# GSM-Board.net
KiCad netlist of a schematic drawn in Altium Designer
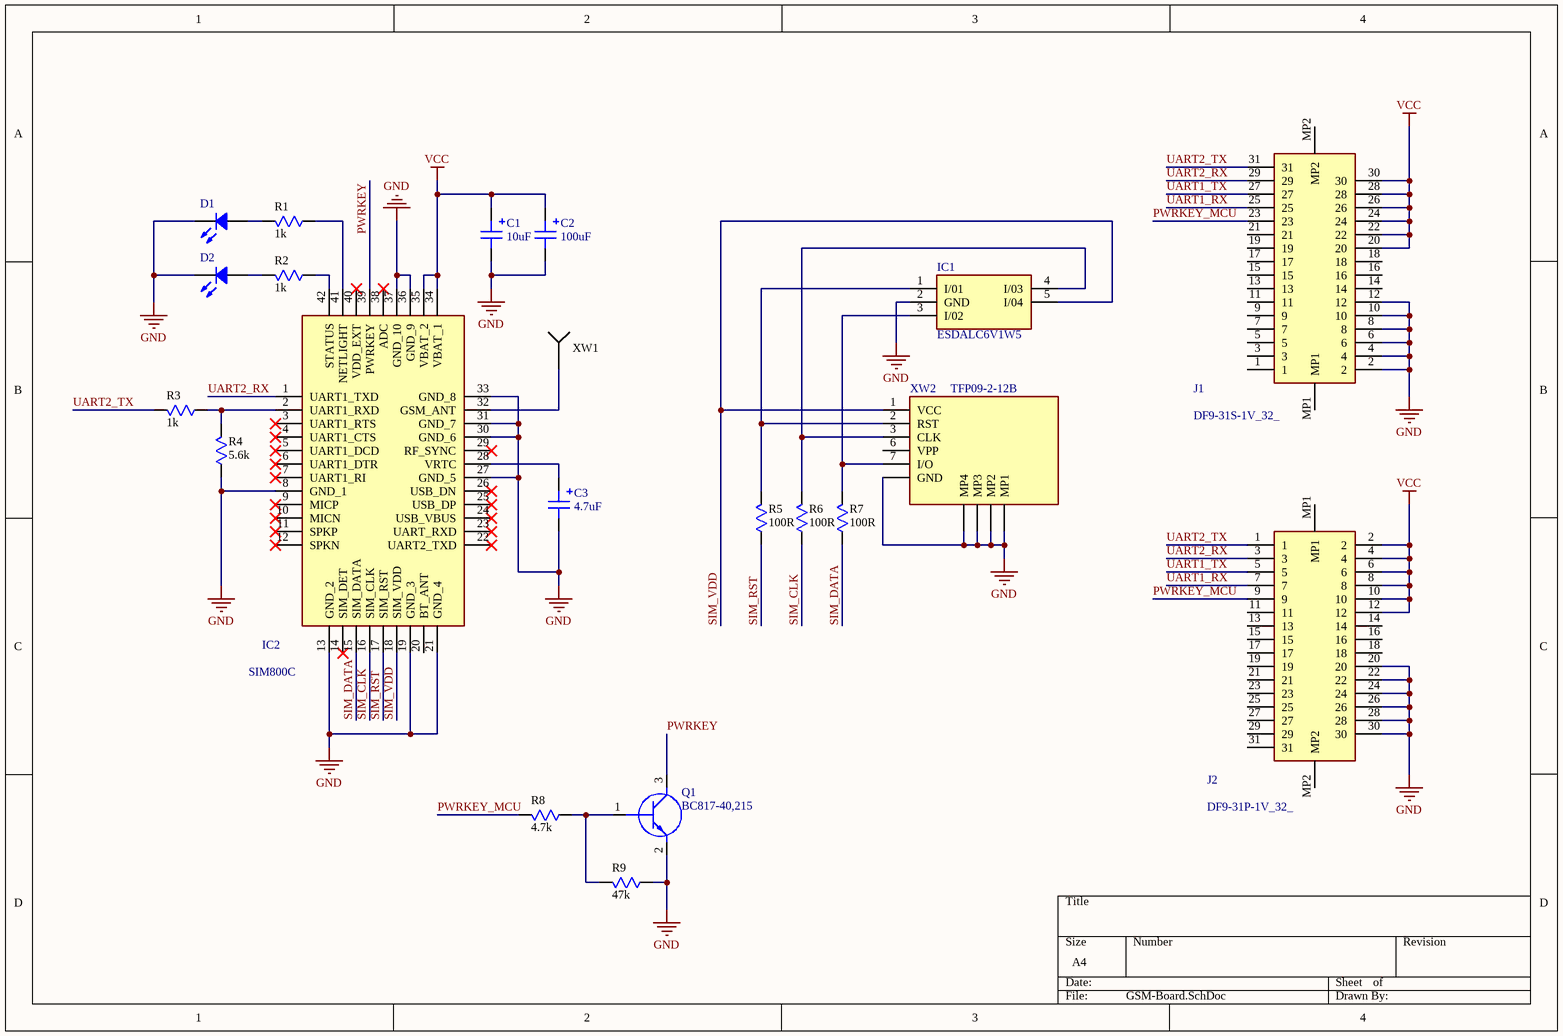
[diagram p0: GSM-Board.SchDoc]

(export (version "E")
  (design (tool "Eeschema 10.0.6"))
  (components
    (comp (ref "C1")
      (value "10uF")
      (footprint "PcbLib:CAP: TANTAL-B")
      (description "SMD Capacitor Polar")
      (libsource (lib "Schlib") (part "Capacitor_polar"))
    )
    (comp (ref "C2")
      (value "100uF")
      (footprint "PcbLib:CAP: TANTAL-D")
      (description "SMD Capacitor Polar")
      (libsource (lib "Schlib") (part "Capacitor_polar"))
    )
    (comp (ref "C3")
      (value "4.7uF")
      (footprint "PcbLib:CAP: TANTAL-A")
      (description "SMD Capacitor Polar")
      (libsource (lib "Schlib") (part "Capacitor_polar"))
    )
    (comp (ref "D1")
      (value "~")
      (footprint "PcbLib:LED0805")
      (description "Chip LED")
      (libsource (lib "Schlib") (part "LED"))
    )
    (comp (ref "D2")
      (value "~")
      (footprint "PcbLib:LED0805")
      (description "Chip LED")
      (libsource (lib "Schlib") (part "LED"))
    )
    (comp (ref "IC1")
      (value "ESDALC6V1W5")
      (footprint "PcbLib:SOT65P210X110-5N")
      (description "Integrated Circuit")
      (fields (field (name "MOUSER PART NUMBER") "511-ESDALC6V1W5"))
      (libsource (lib "*") (part "ESDALC6V1W5"))
    )
    (comp (ref "IC2")
      (value "SIM800C")
      (footprint "PcbLib:SIM800C")
      (description "Integrated Circuit")
      (fields (field (name "MANUFACTURER_PART_NUMBER") "-SIM800C"))
      (libsource (lib "Schlib") (part "-SIM800C"))
    )
    (comp (ref "J1")
      (value "DF9-31S-1V_32_")
      (footprint "PcbLib:DF931S1V32")
      (description "Connector")
      (fields
        (field (name "MANUFACTURER_PART_NUMBER") "DF9-31S-1V(32)")
        (field (name "MOUSER PART NUMBER") "798-DF9-31S-1V32")
      )
      (libsource (lib "Schlib") (part "DF9-31S-1V_32_"))
    )
    (comp (ref "J2")
      (value "DF9-31P-1V_32_")
      (footprint "PcbLib:DF931P1V32")
      (description "Connector")
      (fields
        (field (name "MANUFACTURER_PART_NUMBER") "DF9-31P-1V(32)")
        (field (name "MOUSER PART NUMBER") "798-DF9-31P-1V32")
      )
      (libsource (lib "Schlib") (part "DF9-31P-1V_32_"))
    )
    (comp (ref "Q1")
      (value "BC817-40,215")
      (footprint "PcbLib:BC81740215")
      (description "Transistor BJT NPN")
      (fields (field (name "MOUSER PART NUMBER") "771-BC817-40-T/R"))
      (libsource (lib "*") (part "BC817-40,215"))
    )
    (comp (ref "R1")
      (value "1k")
      (footprint "PcbLib:RES: 0805")
      (fields
        (field (name "MANUFACTURER") "Yageo")
        (field (name "PARTNUMBER") "RC0201JR-07100RL")
        (field (name "VALUEMANUFACTURERPARTNUMBER") "Resistor film, 1k, , 0201, 0.05W, -55...+125°C")
      )
      (libsource (lib "Schlib") (part "Resistor"))
    )
    (comp (ref "R2")
      (value "1k")
      (footprint "PcbLib:RES: 0805")
      (fields
        (field (name "MANUFACTURER") "Yageo")
        (field (name "PARTNUMBER") "RC0201JR-07100RL")
        (field (name "VALUEMANUFACTURERPARTNUMBER") "Resistor film, 1k, , 0201, 0.05W, -55...+125°C")
      )
      (libsource (lib "Schlib") (part "Resistor"))
    )
    (comp (ref "R3")
      (value "1k")
      (footprint "PcbLib:RES: 0805")
      (fields
        (field (name "MANUFACTURER") "Yageo")
        (field (name "PARTNUMBER") "RC0201JR-07100RL")
        (field (name "VALUEMANUFACTURERPARTNUMBER") "Resistor film, 1k, , 0201, 0.05W, -55...+125°C")
      )
      (libsource (lib "Schlib") (part "Resistor"))
    )
    (comp (ref "R4")
      (value "5.6k")
      (footprint "PcbLib:RES: 0805")
      (fields
        (field (name "MANUFACTURER") "Yageo")
        (field (name "PARTNUMBER") "RC0201JR-07100RL")
        (field (name "VALUEMANUFACTURERPARTNUMBER") "Resistor film, 5.6k, , 0201, 0.05W, -55...+125°C")
      )
      (libsource (lib "Schlib") (part "Resistor"))
    )
    (comp (ref "R5")
      (value "100R")
      (footprint "PcbLib:RES: 0805")
      (fields
        (field (name "MANUFACTURER") "Yageo")
        (field (name "PARTNUMBER") "RC0201JR-07100RL")
        (field (name "VALUEMANUFACTURERPARTNUMBER") "Resistor film, 100R, , 0201, 0.05W, -55...+125°C")
      )
      (libsource (lib "Schlib") (part "Resistor"))
    )
    (comp (ref "R6")
      (value "100R")
      (footprint "PcbLib:RES: 0805")
      (fields
        (field (name "MANUFACTURER") "Yageo")
        (field (name "PARTNUMBER") "RC0201JR-07100RL")
        (field (name "VALUEMANUFACTURERPARTNUMBER") "Resistor film, 100R, , 0201, 0.05W, -55...+125°C")
      )
      (libsource (lib "Schlib") (part "Resistor"))
    )
    (comp (ref "R7")
      (value "100R")
      (footprint "PcbLib:RES: 0805")
      (fields
        (field (name "MANUFACTURER") "Yageo")
        (field (name "PARTNUMBER") "RC0201JR-07100RL")
        (field (name "VALUEMANUFACTURERPARTNUMBER") "Resistor film, 100R, , 0201, 0.05W, -55...+125°C")
      )
      (libsource (lib "Schlib") (part "Resistor"))
    )
    (comp (ref "R8")
      (value "4.7k")
      (footprint "PcbLib:RES: 0805")
      (fields
        (field (name "MANUFACTURER") "Yageo")
        (field (name "PARTNUMBER") "RC0201JR-07100RL")
        (field (name "VALUEMANUFACTURERPARTNUMBER") "Resistor film, 4.7k, , 0201, 0.05W, -55...+125°C")
      )
      (libsource (lib "Schlib") (part "Resistor"))
    )
    (comp (ref "R9")
      (value "47k")
      (footprint "PcbLib:RES: 0805")
      (fields
        (field (name "MANUFACTURER") "Yageo")
        (field (name "PARTNUMBER") "RC0201JR-07100RL")
        (field (name "VALUEMANUFACTURERPARTNUMBER") "Resistor film, 47k, , 0201, 0.05W, -55...+125°C")
      )
      (libsource (lib "Schlib") (part "Resistor"))
    )
    (comp (ref "XW1")
      (value "~")
      (footprint "PcbLib:ANT_HOLE")
      (libsource (lib "Schlib") (part "Connector RF"))
    )
    (comp (ref "XW2")
      (value "TFP09-2-12B")
      (footprint "PcbLib:SIMHOLDER")
      (description "Connector")
      (libsource (lib "Schlib") (part "TFP09-2-12B"))
    )
  )
  (nets
    (net (code "1") (name "/PWRKEY") (class "Default")
      (node (ref "IC2") (pin "39") (pinfunction "PWRKEY_39") (pintype "passive"))
      (node (ref "Q1") (pin "3") (pinfunction "C_3") (pintype "passive"))
    )
    (net (code "2") (name "/PWRKEY_MCU") (class "Default")
      (node (ref "J1") (pin "23") (pinfunction "23_23") (pintype "passive"))
      (node (ref "J2") (pin "9") (pinfunction "9_9") (pintype "passive"))
      (node (ref "R8") (pin "2") (pinfunction "2_2") (pintype "passive"))
    )
    (net (code "3") (name "/SIM_CLK") (class "Default")
      (node (ref "IC2") (pin "16") (pinfunction "SIM_CLK_16") (pintype "passive"))
      (node (ref "R6") (pin "1") (pinfunction "1_1") (pintype "passive"))
    )
    (net (code "4") (name "/SIM_DATA") (class "Default")
      (node (ref "IC2") (pin "15") (pinfunction "SIM_DATA_15") (pintype "passive"))
      (node (ref "R7") (pin "1") (pinfunction "1_1") (pintype "passive"))
    )
    (net (code "5") (name "/SIM_RST") (class "Default")
      (node (ref "IC2") (pin "17") (pinfunction "SIM_RST_17") (pintype "passive"))
      (node (ref "R5") (pin "1") (pinfunction "1_1") (pintype "passive"))
    )
    (net (code "6") (name "/SIM_VDD") (class "Default")
      (node (ref "IC1") (pin "5") (pinfunction "I/04_5") (pintype "passive"))
      (node (ref "IC2") (pin "18") (pinfunction "SIM_VDD_18") (pintype "passive"))
      (node (ref "XW2") (pin "1") (pinfunction "VCC_1") (pintype "power_in"))
    )
    (net (code "7") (name "/UART1_RX") (class "Default")
      (node (ref "J1") (pin "25") (pinfunction "25_25") (pintype "passive"))
      (node (ref "J2") (pin "7") (pinfunction "7_7") (pintype "passive"))
    )
    (net (code "8") (name "/UART1_TX") (class "Default")
      (node (ref "J1") (pin "27") (pinfunction "27_27") (pintype "passive"))
      (node (ref "J2") (pin "5") (pinfunction "5_5") (pintype "passive"))
    )
    (net (code "9") (name "/UART2_RX") (class "Default")
      (node (ref "IC2") (pin "1") (pinfunction "UART1_TXD_1") (pintype "passive"))
      (node (ref "J1") (pin "29") (pinfunction "29_29") (pintype "passive"))
      (node (ref "J2") (pin "3") (pinfunction "3_3") (pintype "passive"))
    )
    (net (code "10") (name "/UART2_TX") (class "Default")
      (node (ref "J1") (pin "31") (pinfunction "31_31") (pintype "passive"))
      (node (ref "J2") (pin "1") (pinfunction "1_1") (pintype "passive"))
      (node (ref "R3") (pin "2") (pinfunction "2_2") (pintype "passive"))
    )
    (net (code "11") (name "GND") (class "Default")
      (node (ref "C1") (pin "2") (pinfunction "2_2") (pintype "passive"))
      (node (ref "C2") (pin "2") (pinfunction "2_2") (pintype "passive"))
      (node (ref "C3") (pin "2") (pinfunction "2_2") (pintype "passive"))
      (node (ref "D1") (pin "2") (pinfunction "2_2") (pintype "passive"))
      (node (ref "D2") (pin "2") (pinfunction "2_2") (pintype "passive"))
      (node (ref "IC1") (pin "2") (pinfunction "GND_2") (pintype "passive"))
      (node (ref "IC2") (pin "13") (pinfunction "GND_2_13") (pintype "passive"))
      (node (ref "IC2") (pin "19") (pinfunction "GND_3_19") (pintype "passive"))
      (node (ref "IC2") (pin "21") (pinfunction "GND_4_21") (pintype "passive"))
      (node (ref "IC2") (pin "27") (pinfunction "GND_5_27") (pintype "passive"))
      (node (ref "IC2") (pin "30") (pinfunction "GND_6_30") (pintype "passive"))
      (node (ref "IC2") (pin "31") (pinfunction "GND_7_31") (pintype "passive"))
      (node (ref "IC2") (pin "33") (pinfunction "GND_8_33") (pintype "passive"))
      (node (ref "IC2") (pin "36") (pinfunction "GND_9_36") (pintype "passive"))
      (node (ref "IC2") (pin "37") (pinfunction "GND_10_37") (pintype "passive"))
      (node (ref "IC2") (pin "8") (pinfunction "GND_1_8") (pintype "passive"))
      (node (ref "J1") (pin "10") (pinfunction "10_10") (pintype "passive"))
      (node (ref "J1") (pin "12") (pinfunction "12_12") (pintype "passive"))
      (node (ref "J1") (pin "2") (pinfunction "2_2") (pintype "passive"))
      (node (ref "J1") (pin "4") (pinfunction "4_4") (pintype "passive"))
      (node (ref "J1") (pin "6") (pinfunction "6_6") (pintype "passive"))
      (node (ref "J1") (pin "8") (pinfunction "8_8") (pintype "passive"))
      (node (ref "J2") (pin "20") (pinfunction "20_20") (pintype "passive"))
      (node (ref "J2") (pin "22") (pinfunction "22_22") (pintype "passive"))
      (node (ref "J2") (pin "24") (pinfunction "24_24") (pintype "passive"))
      (node (ref "J2") (pin "26") (pinfunction "26_26") (pintype "passive"))
      (node (ref "J2") (pin "28") (pinfunction "28_28") (pintype "passive"))
      (node (ref "J2") (pin "30") (pinfunction "30_30") (pintype "passive"))
      (node (ref "Q1") (pin "2") (pinfunction "E_2") (pintype "passive"))
      (node (ref "R4") (pin "1") (pinfunction "1_1") (pintype "passive"))
      (node (ref "R9") (pin "1") (pinfunction "1_1") (pintype "passive"))
      (node (ref "XW2") (pin "5") (pinfunction "GND_5") (pintype "power_in"))
      (node (ref "XW2") (pin "MP1") (pinfunction "MP1_MP1") (pintype "passive"))
      (node (ref "XW2") (pin "MP2") (pinfunction "MP2_MP2") (pintype "passive"))
      (node (ref "XW2") (pin "MP3") (pinfunction "MP3_MP3") (pintype "passive"))
      (node (ref "XW2") (pin "MP4") (pinfunction "MP4_MP4") (pintype "passive"))
    )
    (net (code "12") (name "Net-(D1-Pad1)") (class "Default")
      (node (ref "D1") (pin "1") (pinfunction "1_1") (pintype "passive"))
      (node (ref "R1") (pin "2") (pinfunction "2_2") (pintype "passive"))
    )
    (net (code "13") (name "Net-(D2-Pad1)") (class "Default")
      (node (ref "D2") (pin "1") (pinfunction "1_1") (pintype "passive"))
      (node (ref "R2") (pin "2") (pinfunction "2_2") (pintype "passive"))
    )
    (net (code "14") (name "Net-(IC1-I{slash}01)") (class "Default")
      (node (ref "IC1") (pin "1") (pinfunction "I/01_1") (pintype "passive"))
      (node (ref "R5") (pin "2") (pinfunction "2_2") (pintype "passive"))
      (node (ref "XW2") (pin "2") (pinfunction "RST_2") (pintype "passive"))
    )
    (net (code "15") (name "Net-(IC1-I{slash}02)") (class "Default")
      (node (ref "IC1") (pin "3") (pinfunction "I/02_3") (pintype "passive"))
      (node (ref "R7") (pin "2") (pinfunction "2_2") (pintype "passive"))
      (node (ref "XW2") (pin "7") (pinfunction "I/O_7") (pintype "passive"))
    )
    (net (code "16") (name "Net-(IC1-I{slash}03)") (class "Default")
      (node (ref "IC1") (pin "4") (pinfunction "I/03_4") (pintype "passive"))
      (node (ref "R6") (pin "2") (pinfunction "2_2") (pintype "passive"))
      (node (ref "XW2") (pin "3") (pinfunction "CLK_3") (pintype "passive"))
    )
    (net (code "17") (name "Net-(IC2-GSM_ANT)") (class "Default")
      (node (ref "IC2") (pin "32") (pinfunction "GSM_ANT_32") (pintype "passive"))
      (node (ref "XW1") (pin "1") (pinfunction "SIG_1") (pintype "passive"))
    )
    (net (code "18") (name "Net-(IC2-NETLIGHT)") (class "Default")
      (node (ref "IC2") (pin "41") (pinfunction "NETLIGHT_41") (pintype "passive"))
      (node (ref "R1") (pin "1") (pinfunction "1_1") (pintype "passive"))
    )
    (net (code "19") (name "Net-(IC2-STATUS)") (class "Default")
      (node (ref "IC2") (pin "42") (pinfunction "STATUS_42") (pintype "passive"))
      (node (ref "R2") (pin "1") (pinfunction "1_1") (pintype "passive"))
    )
    (net (code "20") (name "Net-(IC2-UART1_RXD)") (class "Default")
      (node (ref "IC2") (pin "2") (pinfunction "UART1_RXD_2") (pintype "passive"))
      (node (ref "R3") (pin "1") (pinfunction "1_1") (pintype "passive"))
      (node (ref "R4") (pin "2") (pinfunction "2_2") (pintype "passive"))
    )
    (net (code "21") (name "Net-(IC2-VRTC)") (class "Default")
      (node (ref "C3") (pin "1") (pinfunction "1_1") (pintype "passive"))
      (node (ref "IC2") (pin "28") (pinfunction "VRTC_28") (pintype "passive"))
    )
    (net (code "22") (name "Net-(Q1-B)") (class "Default")
      (node (ref "Q1") (pin "1") (pinfunction "B_1") (pintype "passive"))
      (node (ref "R8") (pin "1") (pinfunction "1_1") (pintype "passive"))
      (node (ref "R9") (pin "2") (pinfunction "2_2") (pintype "passive"))
    )
    (net (code "23") (name "VCC") (class "Default")
      (node (ref "C1") (pin "1") (pinfunction "1_1") (pintype "passive"))
      (node (ref "C2") (pin "1") (pinfunction "1_1") (pintype "passive"))
      (node (ref "IC2") (pin "34") (pinfunction "VBAT_1_34") (pintype "passive"))
      (node (ref "IC2") (pin "35") (pinfunction "VBAT_2_35") (pintype "passive"))
      (node (ref "J1") (pin "20") (pinfunction "20_20") (pintype "passive"))
      (node (ref "J1") (pin "22") (pinfunction "22_22") (pintype "passive"))
      (node (ref "J1") (pin "24") (pinfunction "24_24") (pintype "passive"))
      (node (ref "J1") (pin "26") (pinfunction "26_26") (pintype "passive"))
      (node (ref "J1") (pin "28") (pinfunction "28_28") (pintype "passive"))
      (node (ref "J1") (pin "30") (pinfunction "30_30") (pintype "passive"))
      (node (ref "J2") (pin "10") (pinfunction "10_10") (pintype "passive"))
      (node (ref "J2") (pin "12") (pinfunction "12_12") (pintype "passive"))
      (node (ref "J2") (pin "2") (pinfunction "2_2") (pintype "passive"))
      (node (ref "J2") (pin "4") (pinfunction "4_4") (pintype "passive"))
      (node (ref "J2") (pin "6") (pinfunction "6_6") (pintype "passive"))
      (node (ref "J2") (pin "8") (pinfunction "8_8") (pintype "passive"))
    )
    (net (code "24") (name "unconnected-(IC2-ADC-Pad38)") (class "Default")
      (node (ref "IC2") (pin "38") (pinfunction "ADC_38") (pintype "passive+no_connect"))
    )
    (net (code "25") (name "unconnected-(IC2-BT_ANT-Pad20)") (class "Default")
      (node (ref "IC2") (pin "20") (pinfunction "BT_ANT_20") (pintype "passive"))
    )
    (net (code "26") (name "unconnected-(IC2-MICN-Pad10)") (class "Default")
      (node (ref "IC2") (pin "10") (pinfunction "MICN_10") (pintype "passive+no_connect"))
    )
    (net (code "27") (name "unconnected-(IC2-MICP-Pad9)") (class "Default")
      (node (ref "IC2") (pin "9") (pinfunction "MICP_9") (pintype "passive+no_connect"))
    )
    (net (code "28") (name "unconnected-(IC2-RF_SYNC-Pad29)") (class "Default")
      (node (ref "IC2") (pin "29") (pinfunction "RF_SYNC_29") (pintype "passive+no_connect"))
    )
    (net (code "29") (name "unconnected-(IC2-SIM_DET-Pad14)") (class "Default")
      (node (ref "IC2") (pin "14") (pinfunction "SIM_DET_14") (pintype "passive+no_connect"))
    )
    (net (code "30") (name "unconnected-(IC2-SPKN-Pad12)") (class "Default")
      (node (ref "IC2") (pin "12") (pinfunction "SPKN_12") (pintype "passive+no_connect"))
    )
    (net (code "31") (name "unconnected-(IC2-SPKP-Pad11)") (class "Default")
      (node (ref "IC2") (pin "11") (pinfunction "SPKP_11") (pintype "passive+no_connect"))
    )
    (net (code "32") (name "unconnected-(IC2-UART1_CTS-Pad4)") (class "Default")
      (node (ref "IC2") (pin "4") (pinfunction "UART1_CTS_4") (pintype "passive+no_connect"))
    )
    (net (code "33") (name "unconnected-(IC2-UART1_DCD-Pad5)") (class "Default")
      (node (ref "IC2") (pin "5") (pinfunction "UART1_DCD_5") (pintype "passive+no_connect"))
    )
    (net (code "34") (name "unconnected-(IC2-UART1_DTR-Pad6)") (class "Default")
      (node (ref "IC2") (pin "6") (pinfunction "UART1_DTR_6") (pintype "passive+no_connect"))
    )
    (net (code "35") (name "unconnected-(IC2-UART1_RI-Pad7)") (class "Default")
      (node (ref "IC2") (pin "7") (pinfunction "UART1_RI_7") (pintype "passive+no_connect"))
    )
    (net (code "36") (name "unconnected-(IC2-UART1_RTS-Pad3)") (class "Default")
      (node (ref "IC2") (pin "3") (pinfunction "UART1_RTS_3") (pintype "passive+no_connect"))
    )
    (net (code "37") (name "unconnected-(IC2-UART2_TXD-Pad22)") (class "Default")
      (node (ref "IC2") (pin "22") (pinfunction "UART2_TXD_22") (pintype "passive+no_connect"))
    )
    (net (code "38") (name "unconnected-(IC2-UART_RXD-Pad23)") (class "Default")
      (node (ref "IC2") (pin "23") (pinfunction "UART_RXD_23") (pintype "passive+no_connect"))
    )
    (net (code "39") (name "unconnected-(IC2-USB_DN-Pad26)") (class "Default")
      (node (ref "IC2") (pin "26") (pinfunction "USB_DN_26") (pintype "passive+no_connect"))
    )
    (net (code "40") (name "unconnected-(IC2-USB_DP-Pad25)") (class "Default")
      (node (ref "IC2") (pin "25") (pinfunction "USB_DP_25") (pintype "passive+no_connect"))
    )
    (net (code "41") (name "unconnected-(IC2-USB_VBUS-Pad24)") (class "Default")
      (node (ref "IC2") (pin "24") (pinfunction "USB_VBUS_24") (pintype "passive+no_connect"))
    )
    (net (code "42") (name "unconnected-(IC2-VDD_EXT-Pad40)") (class "Default")
      (node (ref "IC2") (pin "40") (pinfunction "VDD_EXT_40") (pintype "passive+no_connect"))
    )
    (net (code "43") (name "unconnected-(J1-Pad1)") (class "Default")
      (node (ref "J1") (pin "1") (pinfunction "1_1") (pintype "passive"))
    )
    (net (code "44") (name "unconnected-(J1-Pad3)") (class "Default")
      (node (ref "J1") (pin "3") (pinfunction "3_3") (pintype "passive"))
    )
    (net (code "45") (name "unconnected-(J1-Pad5)") (class "Default")
      (node (ref "J1") (pin "5") (pinfunction "5_5") (pintype "passive"))
    )
    (net (code "46") (name "unconnected-(J1-Pad7)") (class "Default")
      (node (ref "J1") (pin "7") (pinfunction "7_7") (pintype "passive"))
    )
    (net (code "47") (name "unconnected-(J1-Pad9)") (class "Default")
      (node (ref "J1") (pin "9") (pinfunction "9_9") (pintype "passive"))
    )
    (net (code "48") (name "unconnected-(J1-Pad11)") (class "Default")
      (node (ref "J1") (pin "11") (pinfunction "11_11") (pintype "passive"))
    )
    (net (code "49") (name "unconnected-(J1-Pad13)") (class "Default")
      (node (ref "J1") (pin "13") (pinfunction "13_13") (pintype "passive"))
    )
    (net (code "50") (name "unconnected-(J1-Pad14)") (class "Default")
      (node (ref "J1") (pin "14") (pinfunction "14_14") (pintype "passive"))
    )
    (net (code "51") (name "unconnected-(J1-Pad15)") (class "Default")
      (node (ref "J1") (pin "15") (pinfunction "15_15") (pintype "passive"))
    )
    (net (code "52") (name "unconnected-(J1-Pad16)") (class "Default")
      (node (ref "J1") (pin "16") (pinfunction "16_16") (pintype "passive"))
    )
    (net (code "53") (name "unconnected-(J1-Pad17)") (class "Default")
      (node (ref "J1") (pin "17") (pinfunction "17_17") (pintype "passive"))
    )
    (net (code "54") (name "unconnected-(J1-Pad18)") (class "Default")
      (node (ref "J1") (pin "18") (pinfunction "18_18") (pintype "passive"))
    )
    (net (code "55") (name "unconnected-(J1-Pad19)") (class "Default")
      (node (ref "J1") (pin "19") (pinfunction "19_19") (pintype "passive"))
    )
    (net (code "56") (name "unconnected-(J1-Pad21)") (class "Default")
      (node (ref "J1") (pin "21") (pinfunction "21_21") (pintype "passive"))
    )
    (net (code "57") (name "unconnected-(J1-PadMP1)") (class "Default")
      (node (ref "J1") (pin "MP1") (pinfunction "MP1_MP1") (pintype "passive"))
    )
    (net (code "58") (name "unconnected-(J1-PadMP2)") (class "Default")
      (node (ref "J1") (pin "MP2") (pinfunction "MP2_MP2") (pintype "passive"))
    )
    (net (code "59") (name "unconnected-(J2-Pad11)") (class "Default")
      (node (ref "J2") (pin "11") (pinfunction "11_11") (pintype "passive"))
    )
    (net (code "60") (name "unconnected-(J2-Pad13)") (class "Default")
      (node (ref "J2") (pin "13") (pinfunction "13_13") (pintype "passive"))
    )
    (net (code "61") (name "unconnected-(J2-Pad14)") (class "Default")
      (node (ref "J2") (pin "14") (pinfunction "14_14") (pintype "passive"))
    )
    (net (code "62") (name "unconnected-(J2-Pad15)") (class "Default")
      (node (ref "J2") (pin "15") (pinfunction "15_15") (pintype "passive"))
    )
    (net (code "63") (name "unconnected-(J2-Pad16)") (class "Default")
      (node (ref "J2") (pin "16") (pinfunction "16_16") (pintype "passive"))
    )
    (net (code "64") (name "unconnected-(J2-Pad17)") (class "Default")
      (node (ref "J2") (pin "17") (pinfunction "17_17") (pintype "passive"))
    )
    (net (code "65") (name "unconnected-(J2-Pad18)") (class "Default")
      (node (ref "J2") (pin "18") (pinfunction "18_18") (pintype "passive"))
    )
    (net (code "66") (name "unconnected-(J2-Pad19)") (class "Default")
      (node (ref "J2") (pin "19") (pinfunction "19_19") (pintype "passive"))
    )
    (net (code "67") (name "unconnected-(J2-Pad21)") (class "Default")
      (node (ref "J2") (pin "21") (pinfunction "21_21") (pintype "passive"))
    )
    (net (code "68") (name "unconnected-(J2-Pad23)") (class "Default")
      (node (ref "J2") (pin "23") (pinfunction "23_23") (pintype "passive"))
    )
    (net (code "69") (name "unconnected-(J2-Pad25)") (class "Default")
      (node (ref "J2") (pin "25") (pinfunction "25_25") (pintype "passive"))
    )
    (net (code "70") (name "unconnected-(J2-Pad27)") (class "Default")
      (node (ref "J2") (pin "27") (pinfunction "27_27") (pintype "passive"))
    )
    (net (code "71") (name "unconnected-(J2-Pad29)") (class "Default")
      (node (ref "J2") (pin "29") (pinfunction "29_29") (pintype "passive"))
    )
    (net (code "72") (name "unconnected-(J2-Pad31)") (class "Default")
      (node (ref "J2") (pin "31") (pinfunction "31_31") (pintype "passive"))
    )
    (net (code "73") (name "unconnected-(J2-PadMP1)") (class "Default")
      (node (ref "J2") (pin "MP1") (pinfunction "MP1_MP1") (pintype "passive"))
    )
    (net (code "74") (name "unconnected-(J2-PadMP2)") (class "Default")
      (node (ref "J2") (pin "MP2") (pinfunction "MP2_MP2") (pintype "passive"))
    )
    (net (code "75") (name "unconnected-(XW2-VPP-Pad6)") (class "Default")
      (node (ref "XW2") (pin "6") (pinfunction "VPP_6") (pintype "passive"))
    )
  )
)
